# USB_HUB.net
KiCad netlist of a schematic drawn in EasyEDA Pro
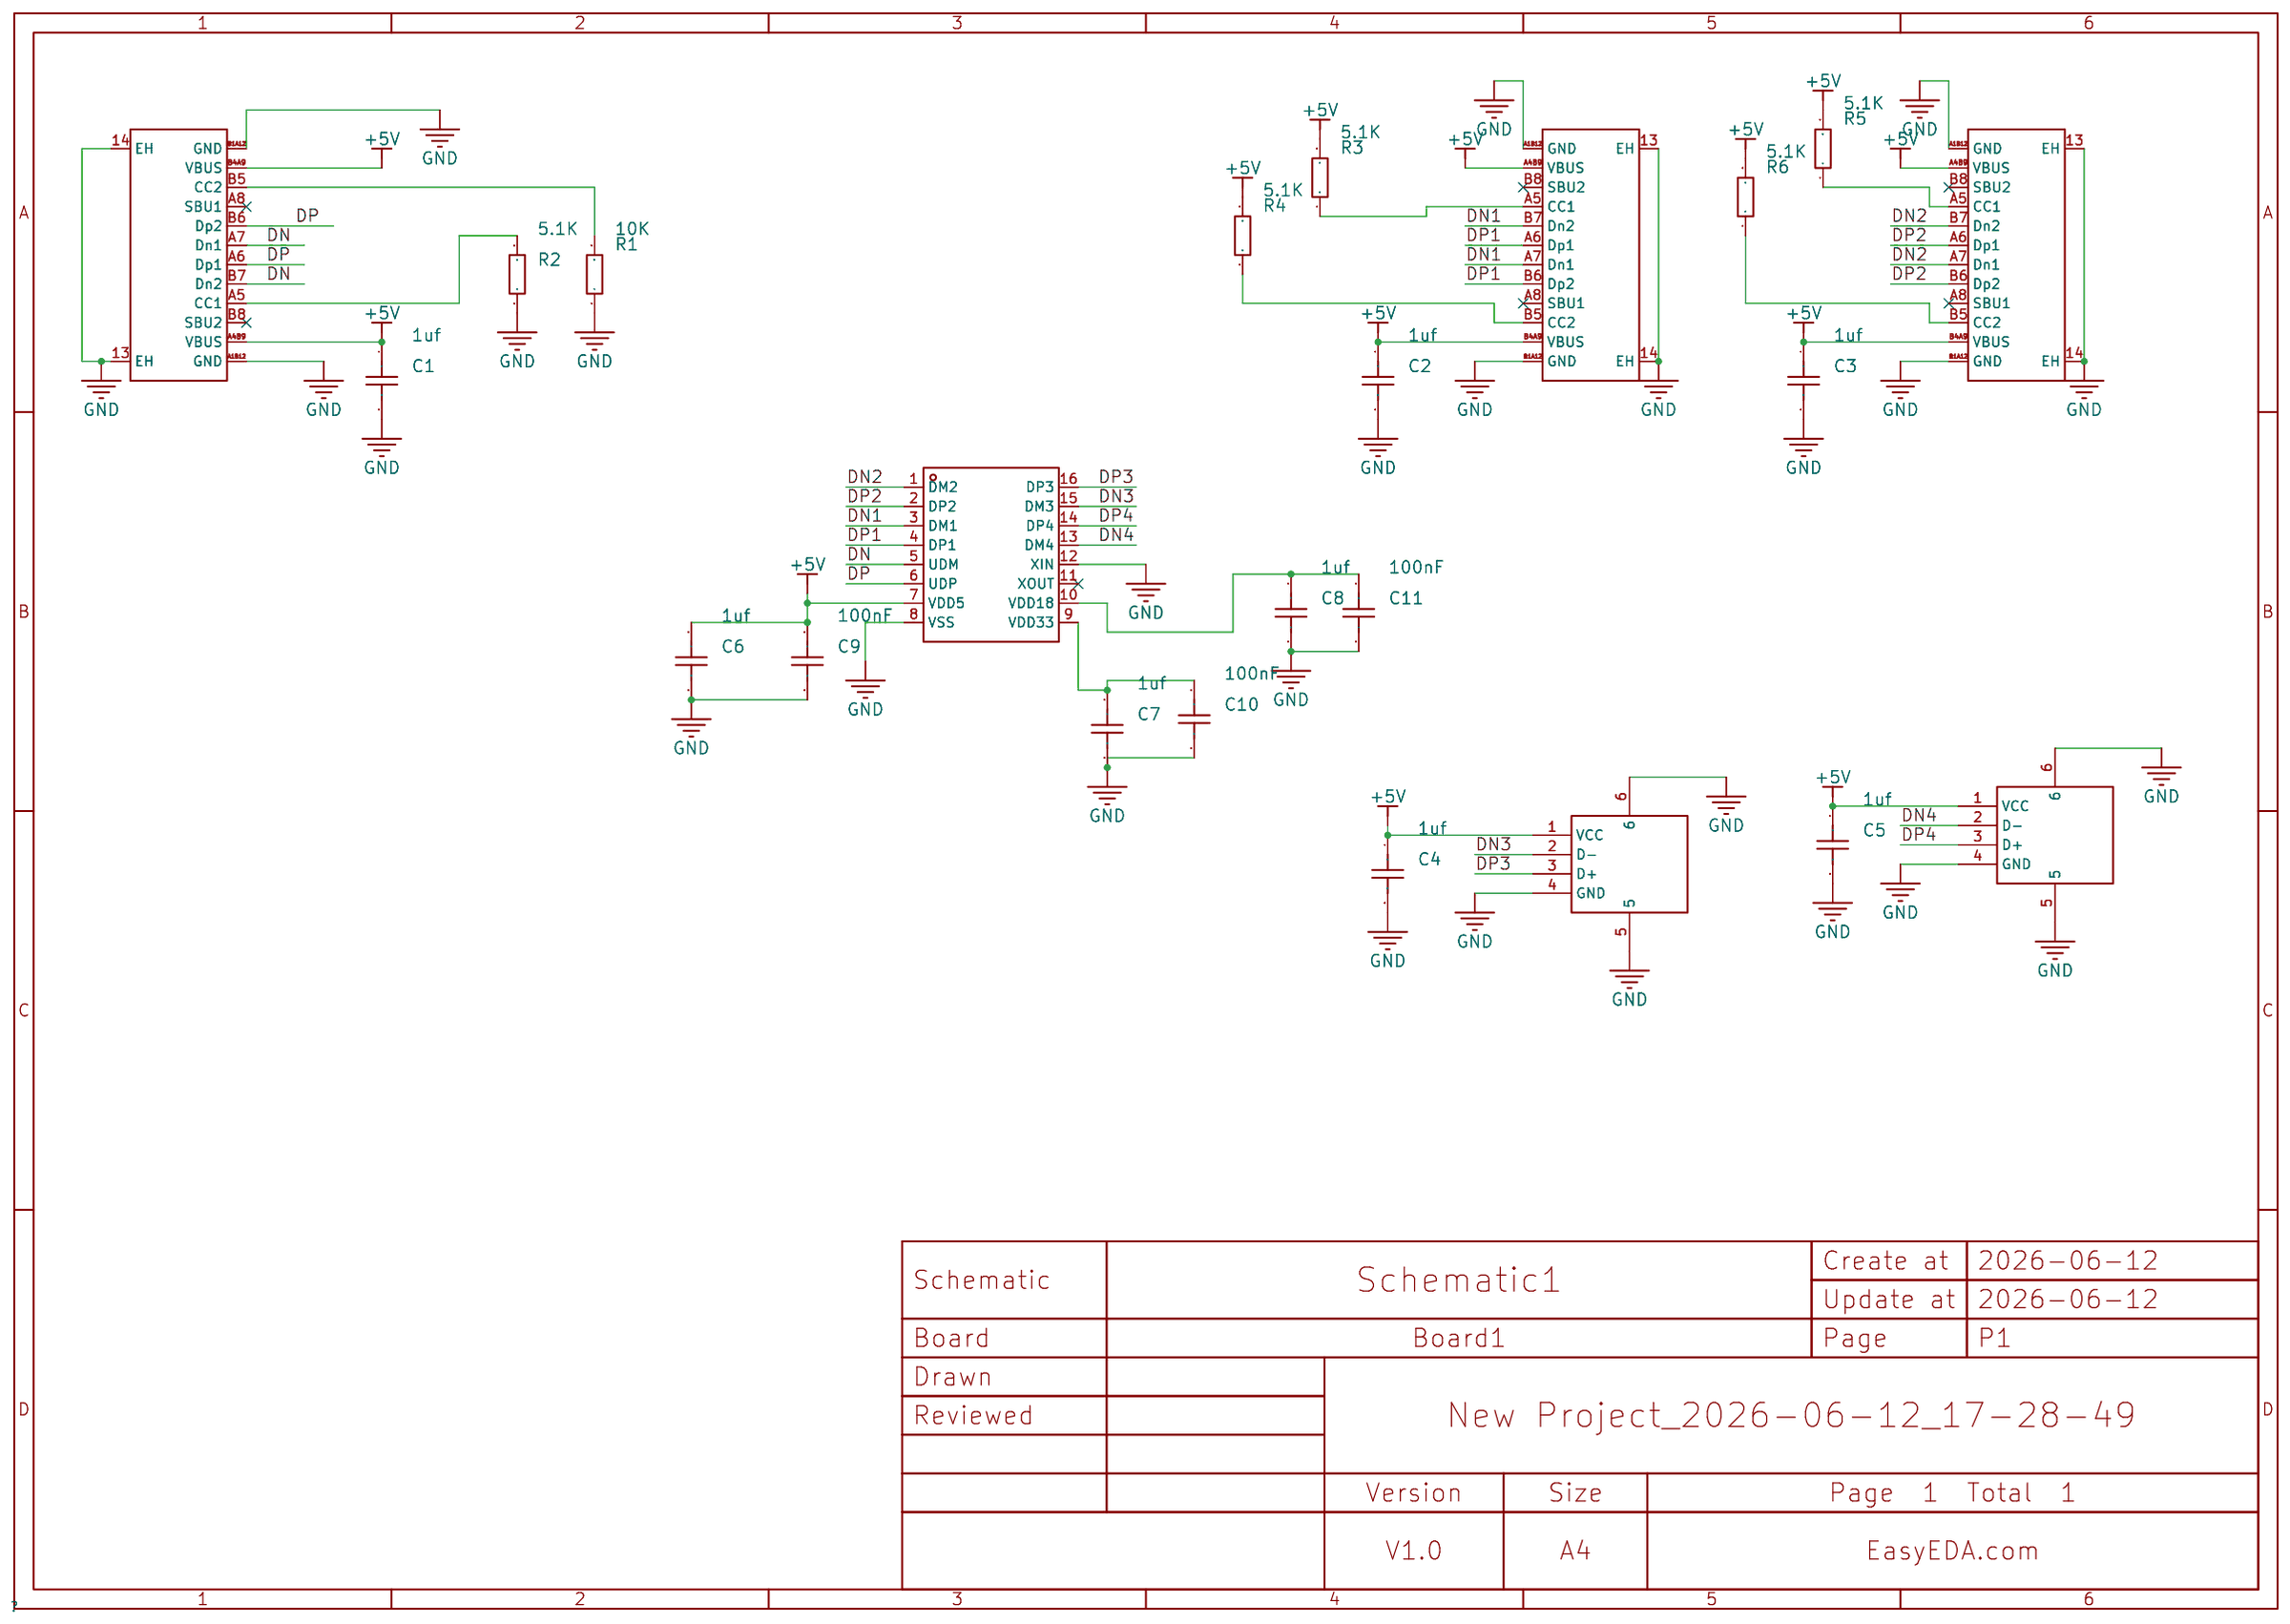
[diagram p0: schematic sheet]

(export (version "E")
  (design (tool "Eeschema 10.0.6"))
  (components
    (comp (ref "C1") (value "1uf") (footprint "easyedapro:C0603") (libsource (lib "easyedapro") (part "CAP")))
    (comp (ref "C2") (value "1uf") (footprint "easyedapro:C0603") (libsource (lib "easyedapro") (part "CAP")))
    (comp (ref "C3") (value "1uf") (footprint "easyedapro:C0603") (libsource (lib "easyedapro") (part "CAP")))
    (comp (ref "C4") (value "1uf") (footprint "easyedapro:C0603") (libsource (lib "easyedapro") (part "CAP")))
    (comp (ref "C5") (value "1uf") (footprint "easyedapro:C0603") (libsource (lib "easyedapro") (part "CAP")))
    (comp (ref "C6") (value "1uf") (footprint "easyedapro:C0603") (libsource (lib "easyedapro") (part "CAP")))
    (comp (ref "C7") (value "1uf") (footprint "easyedapro:C0603") (libsource (lib "easyedapro") (part "CAP")))
    (comp (ref "C8") (value "1uf") (footprint "easyedapro:C0603") (libsource (lib "easyedapro") (part "CAP")))
    (comp (ref "C9")
      (value "100nF")
      (footprint "easyedapro:C0603")
      (libsource (lib "easyedapro") (part "CAP"))
    )
    (comp (ref "C10")
      (value "100nF")
      (footprint "easyedapro:C0603")
      (libsource (lib "easyedapro") (part "CAP"))
    )
    (comp (ref "C11")
      (value "100nF")
      (footprint "easyedapro:C0603")
      (libsource (lib "easyedapro") (part "CAP"))
    )
    (comp (ref "R1") (value "10K") (footprint "easyedapro:R0603") (libsource (lib "easyedapro") (part "Res")))
    (comp (ref "R2")
      (value "5.1K")
      (footprint "easyedapro:R0603")
      (libsource (lib "easyedapro") (part "Res"))
    )
    (comp (ref "R3")
      (value "5.1K")
      (footprint "easyedapro:R0603")
      (libsource (lib "easyedapro") (part "Res"))
    )
    (comp (ref "R4")
      (value "5.1K")
      (footprint "easyedapro:R0603")
      (libsource (lib "easyedapro") (part "Res"))
    )
    (comp (ref "R5")
      (value "5.1K")
      (footprint "easyedapro:R0603")
      (libsource (lib "easyedapro") (part "Res"))
    )
    (comp (ref "R6")
      (value "5.1K")
      (footprint "easyedapro:R0603")
      (libsource (lib "easyedapro") (part "Res"))
    )
    (comp (ref "U1")
      (value "SL2.1s")
      (footprint "easyedapro:SSOP-16_L4.6-W2.6-P0.53-LS4.0-BL")
      (fields (field (name "Manufacturer") "CoreChips(和芯润德)"))
      (libsource (lib "easyedapro") (part "SL2.1S"))
    )
    (comp (ref "USB1")
      (value "TYPE-C 16PIN 2MD(073)")
      (footprint "easyedapro:USB-C-SMD_TYPE-C-16PIN-2MD-073")
      (fields (field (name "Manufacturer") "SHOU HAN(首韩)"))
      (libsource (lib "easyedapro") (part "TYPE-C 16PIN 2MD(073)"))
    )
    (comp (ref "USB2")
      (value "TYPE-C 16PIN 2MD(073)")
      (footprint "easyedapro:USB-C-SMD_TYPE-C-16PIN-2MD-073")
      (fields (field (name "Manufacturer") "SHOU HAN(首韩)"))
      (libsource (lib "easyedapro") (part "TYPE-C 16PIN 2MD(073)"))
    )
    (comp (ref "USB3")
      (value "10.0 QHHTZB6.3")
      (footprint "easyedapro:USB-A-TH_10.0QHHTZB6.3")
      (fields (field (name "Manufacturer") "SHOU HAN(首韩)"))
      (libsource (lib "easyedapro") (part "10.0 QHHTZB6.3"))
    )
    (comp (ref "USB4")
      (value "10.0 QHHTZB6.3")
      (footprint "easyedapro:USB-A-TH_10.0QHHTZB6.3")
      (fields (field (name "Manufacturer") "SHOU HAN(首韩)"))
      (libsource (lib "easyedapro") (part "10.0 QHHTZB6.3"))
    )
    (comp (ref "USB5")
      (value "TYPE-C 16PIN 2MD(073)")
      (footprint "easyedapro:USB-C-SMD_TYPE-C-16PIN-2MD-073")
      (fields (field (name "Manufacturer") "SHOU HAN(首韩)"))
      (libsource (lib "easyedapro") (part "TYPE-C 16PIN 2MD(073)"))
    )
  )
  (nets
    (net (code "1") (name "+5V") (class "Default")
      (node (ref "C1") (pin "1") (pinfunction "1_1") (pintype "input"))
      (node (ref "C2") (pin "1") (pinfunction "1_1") (pintype "input"))
      (node (ref "C3") (pin "1") (pinfunction "1_1") (pintype "input"))
      (node (ref "C4") (pin "1") (pinfunction "1_1") (pintype "input"))
      (node (ref "C5") (pin "1") (pinfunction "1_1") (pintype "input"))
      (node (ref "C6") (pin "1") (pinfunction "1_1") (pintype "input"))
      (node (ref "C9") (pin "1") (pinfunction "1_1") (pintype "input"))
      (node (ref "R3") (pin "2") (pinfunction "2_2") (pintype "input"))
      (node (ref "R4") (pin "2") (pinfunction "2_2") (pintype "input"))
      (node (ref "R5") (pin "2") (pinfunction "2_2") (pintype "input"))
      (node (ref "R6") (pin "2") (pinfunction "2_2") (pintype "input"))
      (node (ref "U1") (pin "7") (pinfunction "VDD5_7") (pintype "unspecified"))
      (node (ref "USB1") (pin "A4B9") (pinfunction "VBUS_A4B9") (pintype "unspecified"))
      (node (ref "USB1") (pin "B4A9") (pinfunction "VBUS_B4A9") (pintype "unspecified"))
      (node (ref "USB2") (pin "A4B9") (pinfunction "VBUS_A4B9") (pintype "unspecified"))
      (node (ref "USB2") (pin "B4A9") (pinfunction "VBUS_B4A9") (pintype "unspecified"))
      (node (ref "USB3") (pin "1") (pinfunction "VCC_1") (pintype "unspecified"))
      (node (ref "USB4") (pin "1") (pinfunction "VCC_1") (pintype "unspecified"))
      (node (ref "USB5") (pin "A4B9") (pinfunction "VBUS_A4B9") (pintype "unspecified"))
      (node (ref "USB5") (pin "B4A9") (pinfunction "VBUS_B4A9") (pintype "unspecified"))
    )
    (net (code "2") (name "/DN") (class "Default")
      (node (ref "U1") (pin "5") (pinfunction "UDM_5") (pintype "unspecified"))
      (node (ref "USB5") (pin "A7") (pinfunction "Dn1_A7") (pintype "unspecified"))
      (node (ref "USB5") (pin "B7") (pinfunction "Dn2_B7") (pintype "unspecified"))
    )
    (net (code "3") (name "/DN1") (class "Default")
      (node (ref "U1") (pin "3") (pinfunction "DM1_3") (pintype "unspecified"))
      (node (ref "USB1") (pin "A7") (pinfunction "Dn1_A7") (pintype "unspecified"))
      (node (ref "USB1") (pin "B7") (pinfunction "Dn2_B7") (pintype "unspecified"))
    )
    (net (code "4") (name "/DN2") (class "Default")
      (node (ref "U1") (pin "1") (pinfunction "DM2_1") (pintype "unspecified"))
      (node (ref "USB2") (pin "A7") (pinfunction "Dn1_A7") (pintype "unspecified"))
      (node (ref "USB2") (pin "B7") (pinfunction "Dn2_B7") (pintype "unspecified"))
    )
    (net (code "5") (name "/DN3") (class "Default")
      (node (ref "U1") (pin "15") (pinfunction "DM3_15") (pintype "unspecified"))
      (node (ref "USB3") (pin "2") (pinfunction "D-_2") (pintype "unspecified"))
    )
    (net (code "6") (name "/DN4") (class "Default")
      (node (ref "U1") (pin "13") (pinfunction "DM4_13") (pintype "unspecified"))
      (node (ref "USB4") (pin "2") (pinfunction "D-_2") (pintype "unspecified"))
    )
    (net (code "7") (name "/DP") (class "Default")
      (node (ref "U1") (pin "6") (pinfunction "UDP_6") (pintype "unspecified"))
      (node (ref "USB5") (pin "A6") (pinfunction "Dp1_A6") (pintype "unspecified"))
      (node (ref "USB5") (pin "B6") (pinfunction "Dp2_B6") (pintype "unspecified"))
    )
    (net (code "8") (name "/DP1") (class "Default")
      (node (ref "U1") (pin "4") (pinfunction "DP1_4") (pintype "unspecified"))
      (node (ref "USB1") (pin "A6") (pinfunction "Dp1_A6") (pintype "unspecified"))
      (node (ref "USB1") (pin "B6") (pinfunction "Dp2_B6") (pintype "unspecified"))
    )
    (net (code "9") (name "/DP2") (class "Default")
      (node (ref "U1") (pin "2") (pinfunction "DP2_2") (pintype "unspecified"))
      (node (ref "USB2") (pin "A6") (pinfunction "Dp1_A6") (pintype "unspecified"))
      (node (ref "USB2") (pin "B6") (pinfunction "Dp2_B6") (pintype "unspecified"))
    )
    (net (code "10") (name "/DP3") (class "Default")
      (node (ref "U1") (pin "16") (pinfunction "DP3_16") (pintype "unspecified"))
      (node (ref "USB3") (pin "3") (pinfunction "D+_3") (pintype "unspecified"))
    )
    (net (code "11") (name "/DP4") (class "Default")
      (node (ref "U1") (pin "14") (pinfunction "DP4_14") (pintype "unspecified"))
      (node (ref "USB4") (pin "3") (pinfunction "D+_3") (pintype "unspecified"))
    )
    (net (code "12") (name "GND") (class "Default")
      (node (ref "C1") (pin "2") (pinfunction "2_2") (pintype "input"))
      (node (ref "C10") (pin "2") (pinfunction "2_2") (pintype "input"))
      (node (ref "C11") (pin "2") (pinfunction "2_2") (pintype "input"))
      (node (ref "C2") (pin "2") (pinfunction "2_2") (pintype "input"))
      (node (ref "C3") (pin "2") (pinfunction "2_2") (pintype "input"))
      (node (ref "C4") (pin "2") (pinfunction "2_2") (pintype "input"))
      (node (ref "C5") (pin "2") (pinfunction "2_2") (pintype "input"))
      (node (ref "C6") (pin "2") (pinfunction "2_2") (pintype "input"))
      (node (ref "C7") (pin "2") (pinfunction "2_2") (pintype "input"))
      (node (ref "C8") (pin "2") (pinfunction "2_2") (pintype "input"))
      (node (ref "C9") (pin "2") (pinfunction "2_2") (pintype "input"))
      (node (ref "R1") (pin "1") (pinfunction "1_1") (pintype "input"))
      (node (ref "R2") (pin "1") (pinfunction "1_1") (pintype "input"))
      (node (ref "U1") (pin "12") (pinfunction "XIN_12") (pintype "unspecified"))
      (node (ref "U1") (pin "8") (pinfunction "VSS_8") (pintype "unspecified"))
      (node (ref "USB1") (pin "13") (pinfunction "EH_13") (pintype "unspecified"))
      (node (ref "USB1") (pin "14") (pinfunction "EH_14") (pintype "unspecified"))
      (node (ref "USB1") (pin "A1B12") (pinfunction "GND_A1B12") (pintype "unspecified"))
      (node (ref "USB1") (pin "B1A12") (pinfunction "GND_B1A12") (pintype "unspecified"))
      (node (ref "USB2") (pin "13") (pinfunction "EH_13") (pintype "unspecified"))
      (node (ref "USB2") (pin "14") (pinfunction "EH_14") (pintype "unspecified"))
      (node (ref "USB2") (pin "A1B12") (pinfunction "GND_A1B12") (pintype "unspecified"))
      (node (ref "USB2") (pin "B1A12") (pinfunction "GND_B1A12") (pintype "unspecified"))
      (node (ref "USB3") (pin "4") (pinfunction "GND_4") (pintype "unspecified"))
      (node (ref "USB3") (pin "5") (pinfunction "5_5") (pintype "unspecified"))
      (node (ref "USB3") (pin "6") (pinfunction "6_6") (pintype "unspecified"))
      (node (ref "USB4") (pin "4") (pinfunction "GND_4") (pintype "unspecified"))
      (node (ref "USB4") (pin "5") (pinfunction "5_5") (pintype "unspecified"))
      (node (ref "USB4") (pin "6") (pinfunction "6_6") (pintype "unspecified"))
      (node (ref "USB5") (pin "13") (pinfunction "EH_13") (pintype "unspecified"))
      (node (ref "USB5") (pin "14") (pinfunction "EH_14") (pintype "unspecified"))
      (node (ref "USB5") (pin "A1B12") (pinfunction "GND_A1B12") (pintype "unspecified"))
      (node (ref "USB5") (pin "B1A12") (pinfunction "GND_B1A12") (pintype "unspecified"))
    )
    (net (code "13") (name "Net-(U1-VDD18)") (class "Default")
      (node (ref "C11") (pin "1") (pinfunction "1_1") (pintype "input"))
      (node (ref "C8") (pin "1") (pinfunction "1_1") (pintype "input"))
      (node (ref "U1") (pin "10") (pinfunction "VDD18_10") (pintype "unspecified"))
    )
    (net (code "14") (name "Net-(U1-VDD33)") (class "Default")
      (node (ref "C10") (pin "1") (pinfunction "1_1") (pintype "input"))
      (node (ref "C7") (pin "1") (pinfunction "1_1") (pintype "input"))
      (node (ref "U1") (pin "9") (pinfunction "VDD33_9") (pintype "unspecified"))
    )
    (net (code "15") (name "Net-(USB1-CC1)") (class "Default")
      (node (ref "R3") (pin "1") (pinfunction "1_1") (pintype "input"))
      (node (ref "USB1") (pin "A5") (pinfunction "CC1_A5") (pintype "unspecified"))
    )
    (net (code "16") (name "Net-(USB1-CC2)") (class "Default")
      (node (ref "R4") (pin "1") (pinfunction "1_1") (pintype "input"))
      (node (ref "USB1") (pin "B5") (pinfunction "CC2_B5") (pintype "unspecified"))
    )
    (net (code "17") (name "Net-(USB2-CC1)") (class "Default")
      (node (ref "R5") (pin "1") (pinfunction "1_1") (pintype "input"))
      (node (ref "USB2") (pin "A5") (pinfunction "CC1_A5") (pintype "unspecified"))
    )
    (net (code "18") (name "Net-(USB2-CC2)") (class "Default")
      (node (ref "R6") (pin "1") (pinfunction "1_1") (pintype "input"))
      (node (ref "USB2") (pin "B5") (pinfunction "CC2_B5") (pintype "unspecified"))
    )
    (net (code "19") (name "Net-(USB5-CC1)") (class "Default")
      (node (ref "R2") (pin "2") (pinfunction "2_2") (pintype "input"))
      (node (ref "USB5") (pin "A5") (pinfunction "CC1_A5") (pintype "unspecified"))
    )
    (net (code "20") (name "Net-(USB5-CC2)") (class "Default")
      (node (ref "R1") (pin "2") (pinfunction "2_2") (pintype "input"))
      (node (ref "USB5") (pin "B5") (pinfunction "CC2_B5") (pintype "unspecified"))
    )
    (net (code "21") (name "unconnected-(U1-XOUT-Pad11)") (class "Default")
      (node (ref "U1") (pin "11") (pinfunction "XOUT_11") (pintype "unspecified+no_connect"))
    )
    (net (code "22") (name "unconnected-(USB1-SBU1-PadA8)") (class "Default")
      (node (ref "USB1") (pin "A8") (pinfunction "SBU1_A8") (pintype "unspecified+no_connect"))
    )
    (net (code "23") (name "unconnected-(USB1-SBU2-PadB8)") (class "Default")
      (node (ref "USB1") (pin "B8") (pinfunction "SBU2_B8") (pintype "unspecified+no_connect"))
    )
    (net (code "24") (name "unconnected-(USB2-SBU1-PadA8)") (class "Default")
      (node (ref "USB2") (pin "A8") (pinfunction "SBU1_A8") (pintype "unspecified+no_connect"))
    )
    (net (code "25") (name "unconnected-(USB2-SBU2-PadB8)") (class "Default")
      (node (ref "USB2") (pin "B8") (pinfunction "SBU2_B8") (pintype "unspecified+no_connect"))
    )
    (net (code "26") (name "unconnected-(USB5-SBU1-PadA8)") (class "Default")
      (node (ref "USB5") (pin "A8") (pinfunction "SBU1_A8") (pintype "unspecified+no_connect"))
    )
    (net (code "27") (name "unconnected-(USB5-SBU2-PadB8)") (class "Default")
      (node (ref "USB5") (pin "B8") (pinfunction "SBU2_B8") (pintype "unspecified+no_connect"))
    )
  )
)
